# Master_MicroController_LED.net
KiCad netlist of a schematic drawn in Altium Designer
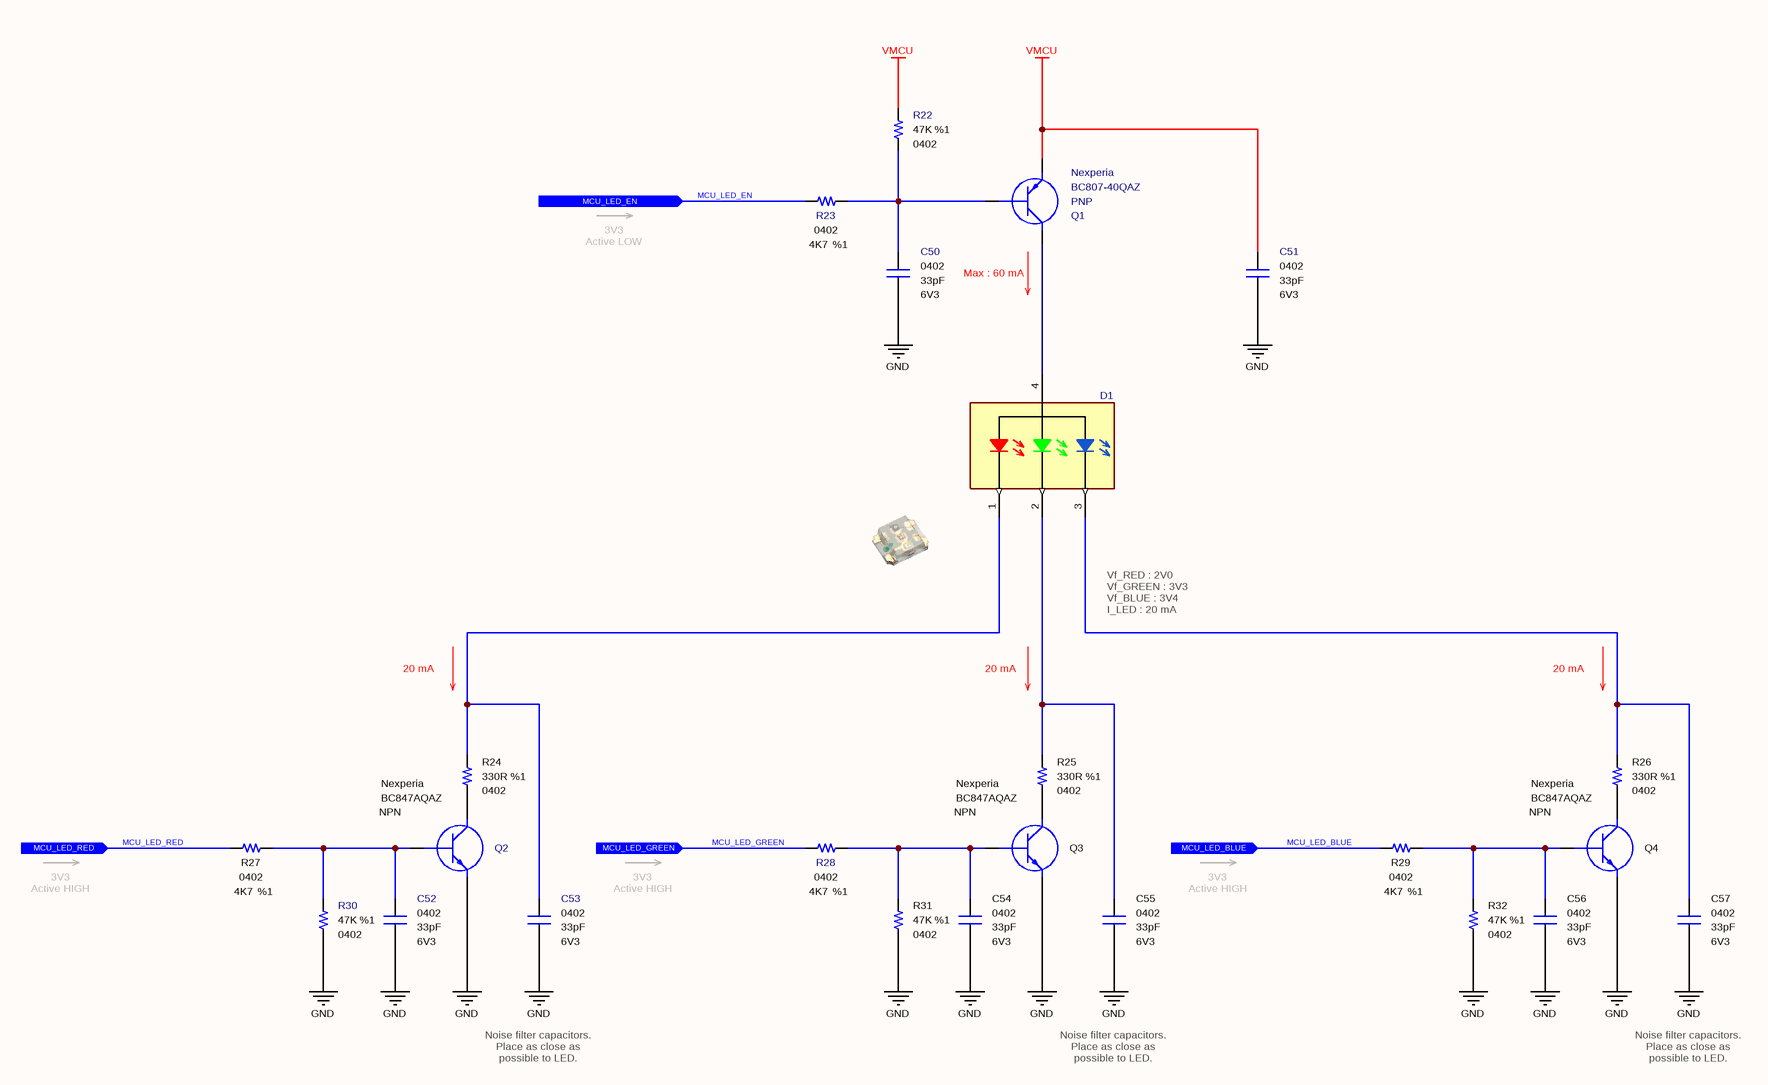
[diagram p0: Master MicroController LED.SchDoc]

(export (version "E")
  (design (tool "Eeschema 10.0.6"))
  (components
    (comp (ref "C50")
      (value "33pF")
      (footprint "CAPACITOR_0402")
      (description "Capacitor - 33pF [0402] (Ceramic)")
      (fields
        (field (name "CASE") "0402")
        (field (name "TOLERANCE") "10%")
        (field (name "VOLTAGE") "6V3")
        (field (name "MANUFACTURER PART NUMBER") "C0402C330J9RACAUTO")
      )
      (libsource (lib "Ovoo_Library") (part "Capacitor - 33pF [0402-6V3]"))
    )
    (comp (ref "C51")
      (value "33pF")
      (footprint "CAPACITOR_0402")
      (description "Capacitor - 33pF [0402] (Ceramic)")
      (fields
        (field (name "CASE") "0402")
        (field (name "TOLERANCE") "10%")
        (field (name "VOLTAGE") "6V3")
        (field (name "MANUFACTURER PART NUMBER") "C0402C330J9RACAUTO")
      )
      (libsource (lib "Ovoo_Library") (part "Capacitor - 33pF [0402-6V3]"))
    )
    (comp (ref "C52")
      (value "33pF")
      (footprint "CAPACITOR_0402")
      (description "Capacitor - 33pF [0402] (Ceramic)")
      (fields
        (field (name "CASE") "0402")
        (field (name "TOLERANCE") "10%")
        (field (name "VOLTAGE") "6V3")
        (field (name "MANUFACTURER PART NUMBER") "C0402C330J9RACAUTO")
      )
      (libsource (lib "Ovoo_Library") (part "Capacitor - 33pF [0402-6V3]"))
    )
    (comp (ref "C53")
      (value "33pF")
      (footprint "CAPACITOR_0402")
      (description "Capacitor - 33pF [0402] (Ceramic)")
      (fields
        (field (name "CASE") "0402")
        (field (name "TOLERANCE") "10%")
        (field (name "VOLTAGE") "6V3")
        (field (name "MANUFACTURER PART NUMBER") "C0402C330J9RACAUTO")
      )
      (libsource (lib "Ovoo_Library") (part "Capacitor - 33pF [0402-6V3]"))
    )
    (comp (ref "C54")
      (value "33pF")
      (footprint "CAPACITOR_0402")
      (description "Capacitor - 33pF [0402] (Ceramic)")
      (fields
        (field (name "CASE") "0402")
        (field (name "TOLERANCE") "10%")
        (field (name "VOLTAGE") "6V3")
        (field (name "MANUFACTURER PART NUMBER") "C0402C330J9RACAUTO")
      )
      (libsource (lib "Ovoo_Library") (part "Capacitor - 33pF [0402-6V3]"))
    )
    (comp (ref "C55")
      (value "33pF")
      (footprint "CAPACITOR_0402")
      (description "Capacitor - 33pF [0402] (Ceramic)")
      (fields
        (field (name "CASE") "0402")
        (field (name "TOLERANCE") "10%")
        (field (name "VOLTAGE") "6V3")
        (field (name "MANUFACTURER PART NUMBER") "C0402C330J9RACAUTO")
      )
      (libsource (lib "Ovoo_Library") (part "Capacitor - 33pF [0402-6V3]"))
    )
    (comp (ref "C56")
      (value "33pF")
      (footprint "CAPACITOR_0402")
      (description "Capacitor - 33pF [0402] (Ceramic)")
      (fields
        (field (name "CASE") "0402")
        (field (name "TOLERANCE") "10%")
        (field (name "VOLTAGE") "6V3")
        (field (name "MANUFACTURER PART NUMBER") "C0402C330J9RACAUTO")
      )
      (libsource (lib "Ovoo_Library") (part "Capacitor - 33pF [0402-6V3]"))
    )
    (comp (ref "C57")
      (value "33pF")
      (footprint "CAPACITOR_0402")
      (description "Capacitor - 33pF [0402] (Ceramic)")
      (fields
        (field (name "CASE") "0402")
        (field (name "TOLERANCE") "10%")
        (field (name "VOLTAGE") "6V3")
        (field (name "MANUFACTURER PART NUMBER") "C0402C330J9RACAUTO")
      )
      (libsource (lib "Ovoo_Library") (part "Capacitor - 33pF [0402-6V3]"))
    )
    (comp (ref "D1")
      (value "150066M153000")
      (footprint "Wurth_0606")
      (description "Standard LEDs - SMD PICOLED series Red LED")
      (fields (field (name "MOUSER PART NUMBER") "710-150066M153000"))
      (libsource (lib "Ovoo_Library") (part "Diode - RGB LED (150066M153000)"))
    )
    (comp (ref "Q1")
      (value "Bipolar PNP Transistors")
      (footprint "SOT1215")
      (description "Bipolar Transistors - BJT 45 V, 500 mA PNP gen purpose transistors")
      (fields
        (field (name "MOUSER PART NUMBER") "771-BC807-40QAZ")
        (field (name "POLARITY") "PNP")
        (field (name "MANUFACTURER NAME") "Nexperia")
        (field (name "MANUFACTURER PART NUMBER") "BC807-40QAZ")
      )
      (libsource (lib "Ovoo_Library") (part "Transistor - BC807"))
    )
    (comp (ref "Q2")
      (value "BC847AQAZ")
      (footprint "SOT1215")
      (description "Bipolar NPN Transistors")
      (fields
        (field (name "POLARITY") "NPN")
        (field (name "MANUFACTURER NAME") "Nexperia")
        (field (name "MANUFACTURER PART NUMBER") "BC847AQAZ")
      )
      (libsource (lib "Ovoo_Library") (part "Transistor - BC847"))
    )
    (comp (ref "Q3")
      (value "BC847AQAZ")
      (footprint "SOT1215")
      (description "Bipolar NPN Transistors")
      (fields
        (field (name "POLARITY") "NPN")
        (field (name "MANUFACTURER NAME") "Nexperia")
        (field (name "MANUFACTURER PART NUMBER") "BC847AQAZ")
      )
      (libsource (lib "Ovoo_Library") (part "Transistor - BC847"))
    )
    (comp (ref "Q4")
      (value "BC847AQAZ")
      (footprint "SOT1215")
      (description "Bipolar NPN Transistors")
      (fields
        (field (name "POLARITY") "NPN")
        (field (name "MANUFACTURER NAME") "Nexperia")
        (field (name "MANUFACTURER PART NUMBER") "BC847AQAZ")
      )
      (libsource (lib "Ovoo_Library") (part "Transistor - BC847"))
    )
    (comp (ref "R22")
      (value "47K")
      (footprint "RESISTOR_0402")
      (description "Thick Film Resistors - SMD 1/16 W 47 Kohms 1%")
      (fields
        (field (name "TOLERANCE") "%1")
        (field (name "CASE") "0402")
        (field (name "MANUFACTURER PART NUMBER") "CRCW040247K0FKED")
        (field (name "Comment") "47K - 0402 - %1 - 1/16W")
      )
      (libsource (lib "Ovoo_Library") (part "Resistor - 47K"))
    )
    (comp (ref "R23")
      (value "4K7")
      (footprint "RESISTOR_0402")
      (description "Thick Film Resistors - SMD 1/16 W 4.7 Kohms 1%")
      (fields
        (field (name "MANUFACTURER PART NUMBER") "CRCW04024K70FKED")
        (field (name "MOUSER PART NUMBER") "71-CRCW0402-4.7K-E3")
        (field (name "TOLERANCE") "%1")
        (field (name "CASE") "0402")
      )
      (libsource (lib "Ovoo_Library") (part "Resistor - 4K7"))
    )
    (comp (ref "R24")
      (value "330R")
      (footprint "RESISTOR_0402")
      (description "Thick Film Resistors - SMD 1/16 W 330 Ohm 1%")
      (fields
        (field (name "MANUFACTURER PART NUMBER") "CRCW0402330RFKED")
        (field (name "MOUSER PART NUMBER") "71-CRCW0402-330-E3")
        (field (name "CASE") "0402")
        (field (name "TOLERANCE") "%1")
      )
      (libsource (lib "Ovoo_Library") (part "Resistor - 330R"))
    )
    (comp (ref "R25")
      (value "330R")
      (footprint "RESISTOR_0402")
      (description "Thick Film Resistors - SMD 1/16 W 330 Ohm 1%")
      (fields
        (field (name "MANUFACTURER PART NUMBER") "CRCW0402330RFKED")
        (field (name "MOUSER PART NUMBER") "71-CRCW0402-330-E3")
        (field (name "CASE") "0402")
        (field (name "TOLERANCE") "%1")
      )
      (libsource (lib "Ovoo_Library") (part "Resistor - 330R"))
    )
    (comp (ref "R26")
      (value "330R")
      (footprint "RESISTOR_0402")
      (description "Thick Film Resistors - SMD 1/16 W 330 Ohm 1%")
      (fields
        (field (name "MANUFACTURER PART NUMBER") "CRCW0402330RFKED")
        (field (name "MOUSER PART NUMBER") "71-CRCW0402-330-E3")
        (field (name "CASE") "0402")
        (field (name "TOLERANCE") "%1")
      )
      (libsource (lib "Ovoo_Library") (part "Resistor - 330R"))
    )
    (comp (ref "R27")
      (value "4K7")
      (footprint "RESISTOR_0402")
      (description "Thick Film Resistors - SMD 1/16 W 4.7 Kohms 1%")
      (fields
        (field (name "MANUFACTURER PART NUMBER") "CRCW04024K70FKED")
        (field (name "MOUSER PART NUMBER") "71-CRCW0402-4.7K-E3")
        (field (name "TOLERANCE") "%1")
        (field (name "CASE") "0402")
      )
      (libsource (lib "Ovoo_Library") (part "Resistor - 4K7"))
    )
    (comp (ref "R28")
      (value "4K7")
      (footprint "RESISTOR_0402")
      (description "Thick Film Resistors - SMD 1/16 W 4.7 Kohms 1%")
      (fields
        (field (name "MANUFACTURER PART NUMBER") "CRCW04024K70FKED")
        (field (name "MOUSER PART NUMBER") "71-CRCW0402-4.7K-E3")
        (field (name "TOLERANCE") "%1")
        (field (name "CASE") "0402")
      )
      (libsource (lib "Ovoo_Library") (part "Resistor - 4K7"))
    )
    (comp (ref "R29")
      (value "4K7")
      (footprint "RESISTOR_0402")
      (description "Thick Film Resistors - SMD 1/16 W 4.7 Kohms 1%")
      (fields
        (field (name "MANUFACTURER PART NUMBER") "CRCW04024K70FKED")
        (field (name "MOUSER PART NUMBER") "71-CRCW0402-4.7K-E3")
        (field (name "TOLERANCE") "%1")
        (field (name "CASE") "0402")
      )
      (libsource (lib "Ovoo_Library") (part "Resistor - 4K7"))
    )
    (comp (ref "R30")
      (value "47K")
      (footprint "RESISTOR_0402")
      (description "Thick Film Resistors - SMD 1/16 W 47 Kohms 1%")
      (fields
        (field (name "TOLERANCE") "%1")
        (field (name "CASE") "0402")
        (field (name "MANUFACTURER PART NUMBER") "CRCW040247K0FKED")
        (field (name "Comment") "47K - 0402 - %1 - 1/16W")
      )
      (libsource (lib "Ovoo_Library") (part "Resistor - 47K"))
    )
    (comp (ref "R31")
      (value "47K")
      (footprint "RESISTOR_0402")
      (description "Thick Film Resistors - SMD 1/16 W 47 Kohms 1%")
      (fields
        (field (name "TOLERANCE") "%1")
        (field (name "CASE") "0402")
        (field (name "MANUFACTURER PART NUMBER") "CRCW040247K0FKED")
        (field (name "Comment") "47K - 0402 - %1 - 1/16W")
      )
      (libsource (lib "Ovoo_Library") (part "Resistor - 47K"))
    )
    (comp (ref "R32")
      (value "47K")
      (footprint "RESISTOR_0402")
      (description "Thick Film Resistors - SMD 1/16 W 47 Kohms 1%")
      (fields
        (field (name "TOLERANCE") "%1")
        (field (name "CASE") "0402")
        (field (name "MANUFACTURER PART NUMBER") "CRCW040247K0FKED")
        (field (name "Comment") "47K - 0402 - %1 - 1/16W")
      )
      (libsource (lib "Ovoo_Library") (part "Resistor - 47K"))
    )
  )
  (nets
    (net (code "1") (name "/MCU_LED_BLUE") (class "Default")
      (node (ref "R29") (pin "2") (pinfunction "2_2") (pintype "passive"))
    )
    (net (code "2") (name "/MCU_LED_EN") (class "Default")
      (node (ref "R23") (pin "2") (pinfunction "2_2") (pintype "passive"))
    )
    (net (code "3") (name "/MCU_LED_GREEN") (class "Default")
      (node (ref "R28") (pin "2") (pinfunction "2_2") (pintype "passive"))
    )
    (net (code "4") (name "/MCU_LED_RED") (class "Default")
      (node (ref "R27") (pin "2") (pinfunction "2_2") (pintype "passive"))
    )
    (net (code "5") (name "GND") (class "Default")
      (node (ref "C50") (pin "2") (pinfunction "2_2") (pintype "passive"))
      (node (ref "C51") (pin "2") (pinfunction "2_2") (pintype "passive"))
      (node (ref "C52") (pin "2") (pinfunction "2_2") (pintype "passive"))
      (node (ref "C53") (pin "2") (pinfunction "2_2") (pintype "passive"))
      (node (ref "C54") (pin "2") (pinfunction "2_2") (pintype "passive"))
      (node (ref "C55") (pin "2") (pinfunction "2_2") (pintype "passive"))
      (node (ref "C56") (pin "2") (pinfunction "2_2") (pintype "passive"))
      (node (ref "C57") (pin "2") (pinfunction "2_2") (pintype "passive"))
      (node (ref "Q2") (pin "2") (pinfunction "E_2") (pintype "passive"))
      (node (ref "Q3") (pin "2") (pinfunction "E_2") (pintype "passive"))
      (node (ref "Q4") (pin "2") (pinfunction "E_2") (pintype "passive"))
      (node (ref "R30") (pin "1") (pinfunction "1_1") (pintype "passive"))
      (node (ref "R31") (pin "1") (pinfunction "1_1") (pintype "passive"))
      (node (ref "R32") (pin "1") (pinfunction "1_1") (pintype "passive"))
    )
    (net (code "6") (name "Net-(C53-Pad1)") (class "Default")
      (node (ref "C53") (pin "1") (pinfunction "1_1") (pintype "passive"))
      (node (ref "D1") (pin "1") (pinfunction "1_1") (pintype "output"))
      (node (ref "R24") (pin "2") (pinfunction "2_2") (pintype "passive"))
    )
    (net (code "7") (name "Net-(C55-Pad1)") (class "Default")
      (node (ref "C55") (pin "1") (pinfunction "1_1") (pintype "passive"))
      (node (ref "D1") (pin "2") (pinfunction "2_2") (pintype "output"))
      (node (ref "R25") (pin "2") (pinfunction "2_2") (pintype "passive"))
    )
    (net (code "8") (name "Net-(C57-Pad1)") (class "Default")
      (node (ref "C57") (pin "1") (pinfunction "1_1") (pintype "passive"))
      (node (ref "D1") (pin "3") (pinfunction "3_3") (pintype "output"))
      (node (ref "R26") (pin "2") (pinfunction "2_2") (pintype "passive"))
    )
    (net (code "9") (name "Net-(Q1-B)") (class "Default")
      (node (ref "C50") (pin "1") (pinfunction "1_1") (pintype "passive"))
      (node (ref "Q1") (pin "1") (pinfunction "B_1") (pintype "passive"))
      (node (ref "R22") (pin "1") (pinfunction "1_1") (pintype "passive"))
      (node (ref "R23") (pin "1") (pinfunction "1_1") (pintype "passive"))
    )
    (net (code "10") (name "Net-(Q1-C)") (class "Default")
      (node (ref "D1") (pin "4") (pinfunction "4_4") (pintype "power_in"))
      (node (ref "Q1") (pin "3") (pinfunction "C_3") (pintype "passive"))
    )
    (net (code "11") (name "Net-(Q2-B)") (class "Default")
      (node (ref "C52") (pin "1") (pinfunction "1_1") (pintype "passive"))
      (node (ref "Q2") (pin "1") (pinfunction "B_1") (pintype "passive"))
      (node (ref "R27") (pin "1") (pinfunction "1_1") (pintype "passive"))
      (node (ref "R30") (pin "2") (pinfunction "2_2") (pintype "passive"))
    )
    (net (code "12") (name "Net-(Q2-C)") (class "Default")
      (node (ref "Q2") (pin "3") (pinfunction "C_3") (pintype "passive"))
      (node (ref "R24") (pin "1") (pinfunction "1_1") (pintype "passive"))
    )
    (net (code "13") (name "Net-(Q3-B)") (class "Default")
      (node (ref "C54") (pin "1") (pinfunction "1_1") (pintype "passive"))
      (node (ref "Q3") (pin "1") (pinfunction "B_1") (pintype "passive"))
      (node (ref "R28") (pin "1") (pinfunction "1_1") (pintype "passive"))
      (node (ref "R31") (pin "2") (pinfunction "2_2") (pintype "passive"))
    )
    (net (code "14") (name "Net-(Q3-C)") (class "Default")
      (node (ref "Q3") (pin "3") (pinfunction "C_3") (pintype "passive"))
      (node (ref "R25") (pin "1") (pinfunction "1_1") (pintype "passive"))
    )
    (net (code "15") (name "Net-(Q4-B)") (class "Default")
      (node (ref "C56") (pin "1") (pinfunction "1_1") (pintype "passive"))
      (node (ref "Q4") (pin "1") (pinfunction "B_1") (pintype "passive"))
      (node (ref "R29") (pin "1") (pinfunction "1_1") (pintype "passive"))
      (node (ref "R32") (pin "2") (pinfunction "2_2") (pintype "passive"))
    )
    (net (code "16") (name "Net-(Q4-C)") (class "Default")
      (node (ref "Q4") (pin "3") (pinfunction "C_3") (pintype "passive"))
      (node (ref "R26") (pin "1") (pinfunction "1_1") (pintype "passive"))
    )
    (net (code "17") (name "VMCU") (class "Default")
      (node (ref "C51") (pin "1") (pinfunction "1_1") (pintype "passive"))
      (node (ref "Q1") (pin "2") (pinfunction "E_2") (pintype "passive"))
      (node (ref "R22") (pin "2") (pinfunction "2_2") (pintype "passive"))
    )
  )
)
